# heatedBed.net
KiCad netlist of a schematic drawn in EAGLE
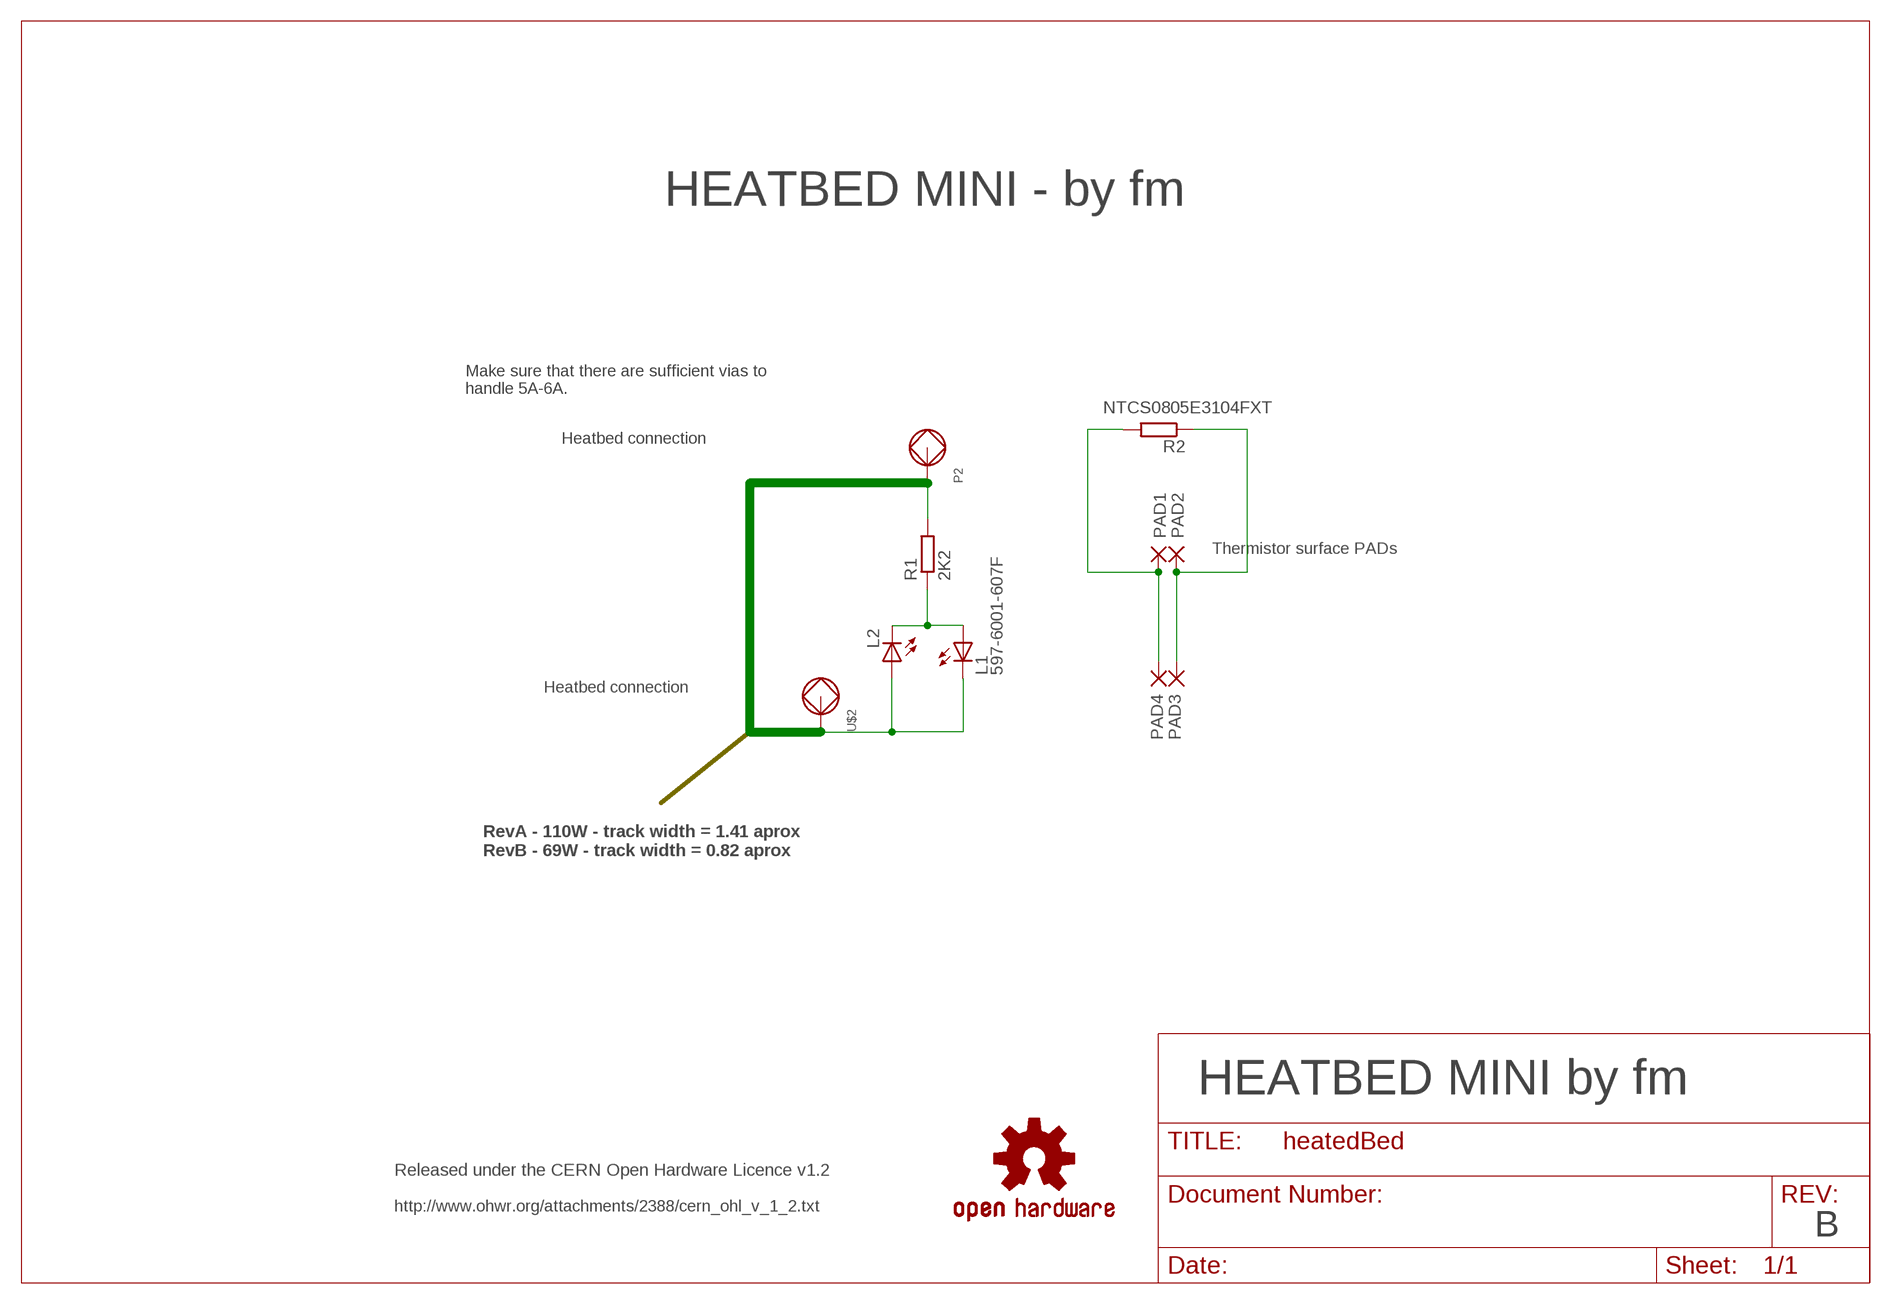
[diagram p0: schematic, sheet 1]

(export (version "E")
  (design (tool "Eeschema 10.0.6"))
  (components
    (comp (ref "L1")
      (value "597-6001-607F")
      (footprint "eagle-import:CHIPLED_1206_REVERSE")
      (libsource (lib "eagle-import") (part "LEDCHIPLED_1206_REV"))
    )
    (comp (ref "L2")
      (value "LEDCHIPLED_1206_REV")
      (footprint "eagle-import:CHIPLED_1206_REVERSE")
      (libsource (lib "eagle-import") (part "LEDCHIPLED_1206_REV"))
    )
    (comp (ref "P2")
      (value "LONG_PAD")
      (footprint "eagle-import:LONG_PAD")
      (libsource (lib "eagle-import") (part "LONG_PAD"))
    )
    (comp (ref "PAD1")
      (value "SMD5")
      (footprint "eagle-import:SMD2,54-5,08")
      (libsource (lib "eagle-import") (part "SMD5"))
    )
    (comp (ref "PAD2")
      (value "SMD5")
      (footprint "eagle-import:SMD2,54-5,08")
      (libsource (lib "eagle-import") (part "SMD5"))
    )
    (comp (ref "PAD3")
      (value "SMD5")
      (footprint "eagle-import:SMD2,54-5,08")
      (libsource (lib "eagle-import") (part "SMD5"))
    )
    (comp (ref "PAD4")
      (value "SMD5")
      (footprint "eagle-import:SMD2,54-5,08")
      (libsource (lib "eagle-import") (part "SMD5"))
    )
    (comp (ref "R1")
      (value "2K2")
      (footprint "eagle-import:R0805")
      (libsource (lib "eagle-import") (part "R-EU_R0805"))
    )
    (comp (ref "R2")
      (value "NTCS0805E3104FXT")
      (footprint "eagle-import:R0805")
      (libsource (lib "eagle-import") (part "R-EU_R0805"))
    )
    (comp (ref "U$2")
      (value "LONG_PAD")
      (footprint "eagle-import:LONG_PAD")
      (libsource (lib "eagle-import") (part "LONG_PAD"))
    )
    (comp (ref "U$5")
      (value "SPARKFUN_OSHW-LOGOL")
      (footprint "eagle-import:SPARKFUN_OSHW-LOGO-L")
      (libsource (lib "eagle-import") (part "SPARKFUN_OSHW-LOGOL"))
    )
  )
  (nets
    (net (code "1") (name "Net-(L1-PadA)") (class "Default")
      (node (ref "L1") (pin "A") (pinfunction "A_A") (pintype "passive"))
      (node (ref "L2") (pin "C") (pinfunction "C_C") (pintype "passive"))
      (node (ref "R1") (pin "1") (pinfunction "1_1") (pintype "passive"))
    )
    (net (code "2") (name "Net-(L1-PadC)") (class "Default")
      (node (ref "L1") (pin "C") (pinfunction "C_C") (pintype "passive"))
      (node (ref "L2") (pin "A") (pinfunction "A_A") (pintype "passive"))
      (node (ref "P2") (pin "P$1") (pinfunction "P$1_P$1") (pintype "bidirectional"))
      (node (ref "P2") (pin "P$2") (pinfunction "P$1_P$2") (pintype "bidirectional"))
      (node (ref "P2") (pin "P$3") (pinfunction "P$1_P$3") (pintype "bidirectional"))
      (node (ref "R1") (pin "2") (pinfunction "2_2") (pintype "passive"))
      (node (ref "U$2") (pin "P$1") (pinfunction "P$1_P$1") (pintype "bidirectional"))
      (node (ref "U$2") (pin "P$2") (pinfunction "P$1_P$2") (pintype "bidirectional"))
      (node (ref "U$2") (pin "P$3") (pinfunction "P$1_P$3") (pintype "bidirectional"))
    )
    (net (code "3") (name "Net-(PAD1-P)") (class "Default")
      (node (ref "PAD1") (pin "1") (pinfunction "P_1") (pintype "passive"))
      (node (ref "PAD4") (pin "1") (pinfunction "P_1") (pintype "passive"))
      (node (ref "R2") (pin "2") (pinfunction "2_2") (pintype "passive"))
    )
    (net (code "4") (name "Net-(PAD2-P)") (class "Default")
      (node (ref "PAD2") (pin "1") (pinfunction "P_1") (pintype "passive"))
      (node (ref "PAD3") (pin "1") (pinfunction "P_1") (pintype "passive"))
      (node (ref "R2") (pin "1") (pinfunction "1_1") (pintype "passive"))
    )
  )
)
